# badge_ver_C.net
KiCad netlist of a schematic drawn in EAGLE
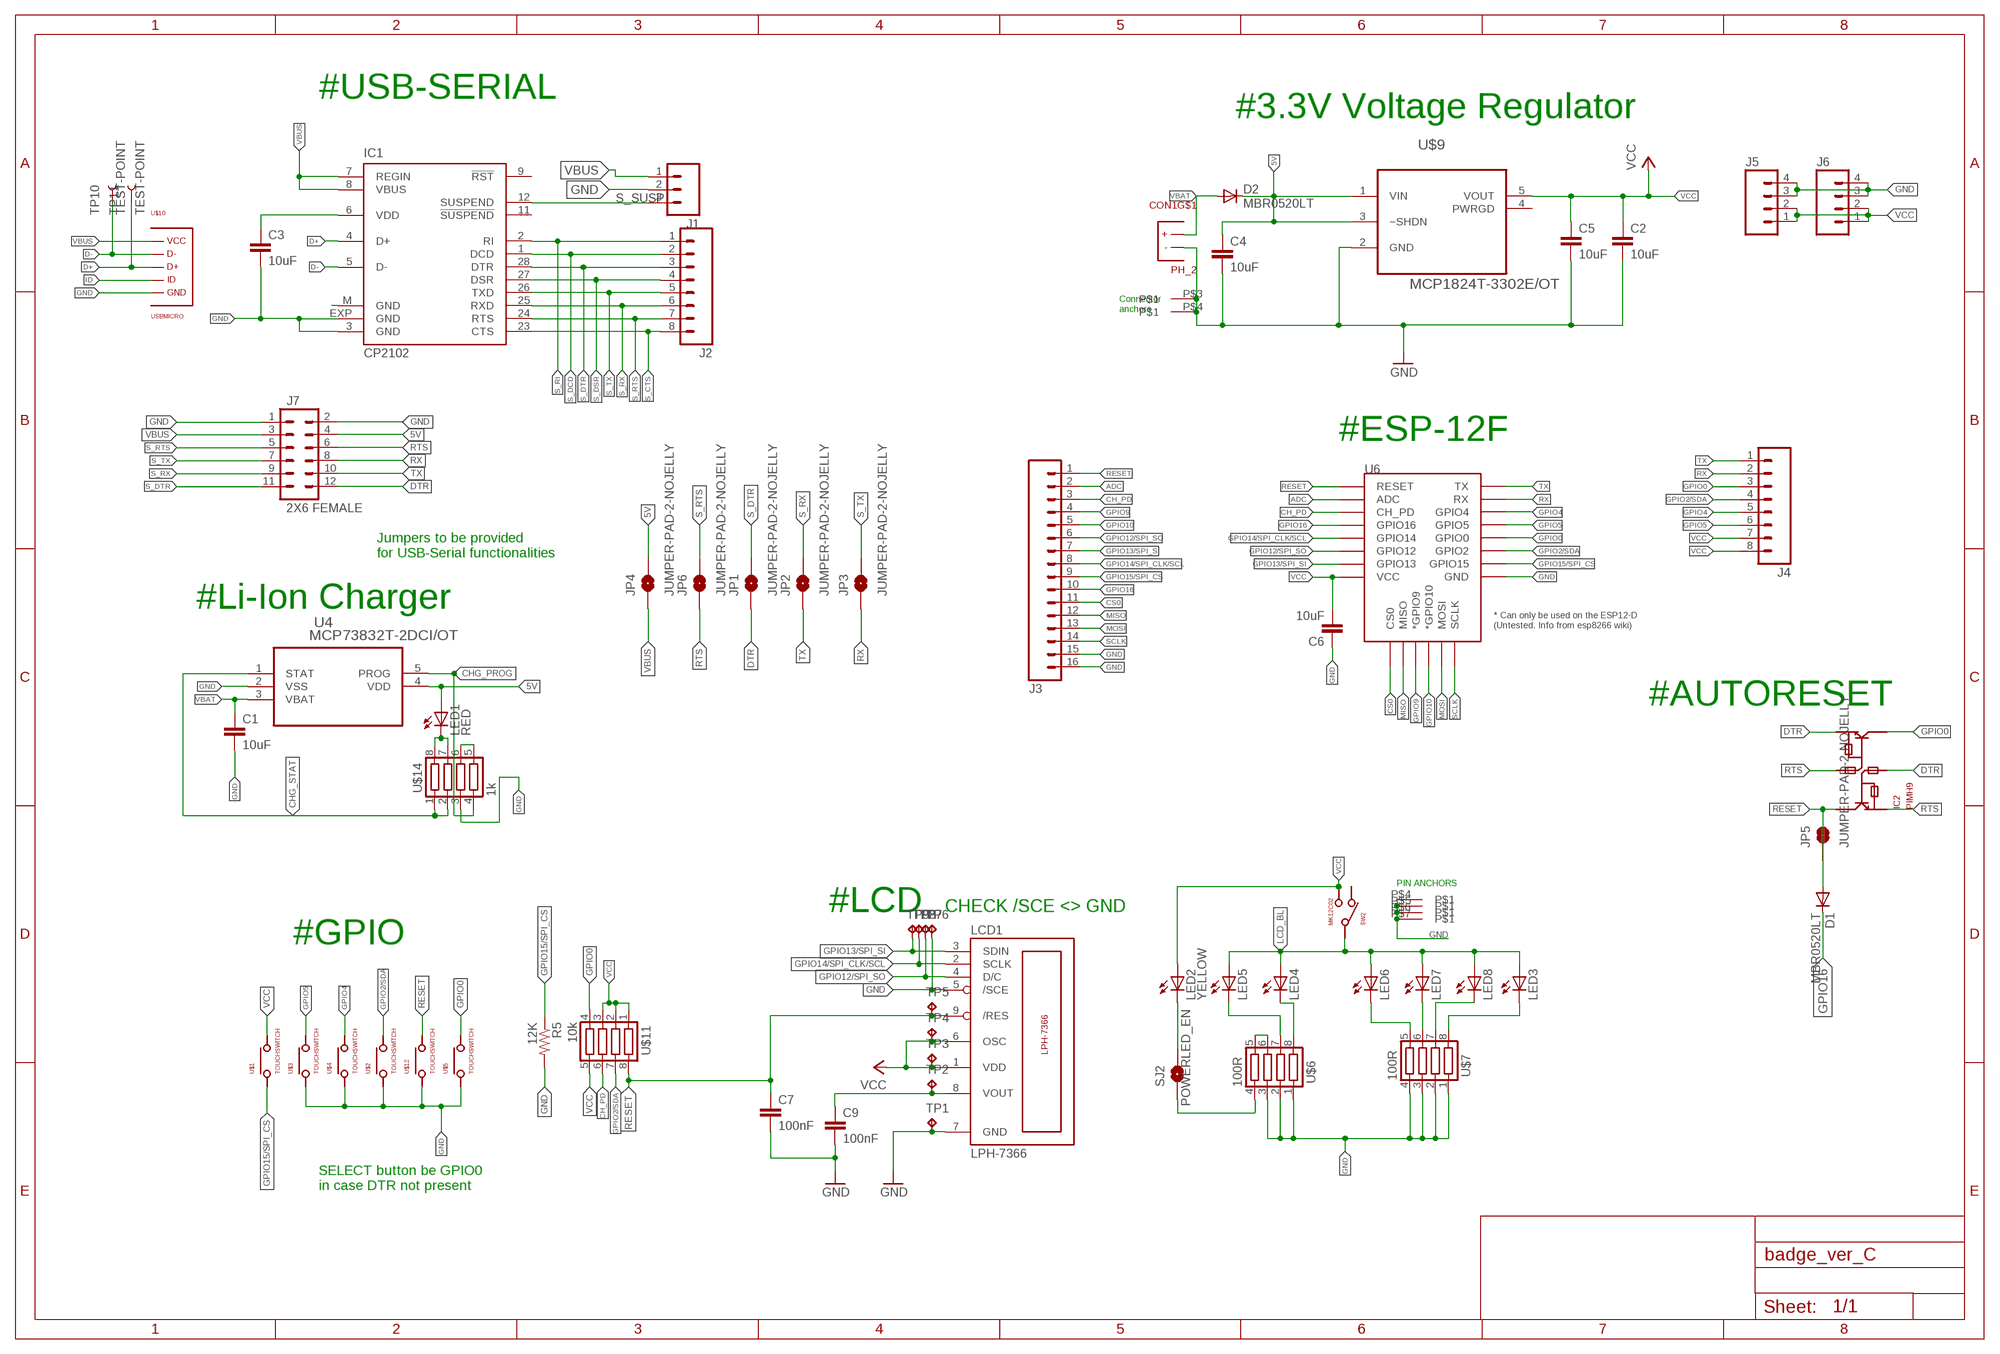
[diagram p0: schematic, sheet 1]

(export (version "E")
  (design (tool "Eeschema 10.0.6"))
  (components
    (comp (ref "C1")
      (value "10uF")
      (footprint "eagle-import:0805-CAP")
      (libsource (lib "eagle-import") (part "1UF-25V-10%(0805){dblquote}"))
    )
    (comp (ref "C2")
      (value "10uF")
      (footprint "eagle-import:0805-CAP")
      (libsource (lib "eagle-import") (part "1UF-25V-10%(0805){dblquote}"))
    )
    (comp (ref "C3")
      (value "10uF")
      (footprint "eagle-import:0805-CAP")
      (libsource (lib "eagle-import") (part "1UF-25V-10%(0805){dblquote}"))
    )
    (comp (ref "C4")
      (value "10uF")
      (footprint "eagle-import:0805-CAP")
      (libsource (lib "eagle-import") (part "1UF-25V-10%(0805){dblquote}"))
    )
    (comp (ref "C5")
      (value "10uF")
      (footprint "eagle-import:0805-CAP")
      (libsource (lib "eagle-import") (part "1UF-25V-10%(0805){dblquote}"))
    )
    (comp (ref "C6")
      (value "10uF")
      (footprint "eagle-import:0805-CAP")
      (libsource (lib "eagle-import") (part "1UF-25V-10%(0805){dblquote}"))
    )
    (comp (ref "C7")
      (value "100nF")
      (footprint "eagle-import:0805-CAP")
      (libsource (lib "eagle-import") (part "1UF-25V-10%(0805){dblquote}"))
    )
    (comp (ref "C9")
      (value "100nF")
      (footprint "eagle-import:0805-CAP")
      (libsource (lib "eagle-import") (part "1UF-25V-10%(0805){dblquote}"))
    )
    (comp (ref "CON1")
      (value "PH_2")
      (footprint "eagle-import:PH_2")
      (libsource (lib "eagle-import") (part "PH_2"))
    )
    (comp (ref "D1")
      (value "MBR0520LT")
      (footprint "eagle-import:SOD123")
      (libsource (lib "eagle-import") (part "MBR0520LT"))
    )
    (comp (ref "D2")
      (value "MBR0520LT")
      (footprint "eagle-import:SOD123")
      (libsource (lib "eagle-import") (part "MBR0520LT"))
    )
    (comp (ref "IC1")
      (value "CP2102")
      (footprint "eagle-import:MLP28")
      (fields (field (name "MF") "FARNELL") (field (name "MPN") "CP2102-GM"))
      (libsource (lib "eagle-import") (part "CP2102"))
    )
    (comp (ref "IC2")
      (value "PIMH9")
      (footprint "eagle-import:SOT457")
      (libsource (lib "eagle-import") (part "PIMH9"))
    )
    (comp (ref "J1")
      (value "M03PTH")
      (footprint "eagle-import:1X03")
      (libsource (lib "eagle-import") (part "M03PTH"))
    )
    (comp (ref "J2")
      (value "M08SILK_FEMALE_PTH")
      (footprint "eagle-import:1X08")
      (libsource (lib "eagle-import") (part "M08SILK_FEMALE_PTH"))
    )
    (comp (ref "J3")
      (value "M16PTH")
      (footprint "eagle-import:1X16")
      (libsource (lib "eagle-import") (part "M16PTH"))
    )
    (comp (ref "J4")
      (value "M08")
      (footprint "eagle-import:1X08_ROUND")
      (libsource (lib "eagle-import") (part "M08"))
    )
    (comp (ref "J5")
      (value "M04PTH")
      (footprint "eagle-import:1X04")
      (libsource (lib "eagle-import") (part "M04PTH"))
    )
    (comp (ref "J6")
      (value "M04PTH")
      (footprint "eagle-import:1X04")
      (libsource (lib "eagle-import") (part "M04PTH"))
    )
    (comp (ref "J7")
      (value "2X6 FEMALE")
      (footprint "eagle-import:2X6")
      (libsource (lib "eagle-import") (part "M06X2PTH_FEMALE"))
    )
    (comp (ref "JP1")
      (value "JUMPER-PAD-2-NOJELLY")
      (footprint "eagle-import:JELLYPAD-JUMPER-2-NO_NO_SILK")
      (libsource (lib "eagle-import") (part "JUMPER-PAD-2-NOJELLY"))
    )
    (comp (ref "JP2")
      (value "JUMPER-PAD-2-NOJELLY")
      (footprint "eagle-import:JELLYPAD-JUMPER-2-NO_NO_SILK")
      (libsource (lib "eagle-import") (part "JUMPER-PAD-2-NOJELLY"))
    )
    (comp (ref "JP3")
      (value "JUMPER-PAD-2-NOJELLY")
      (footprint "eagle-import:JELLYPAD-JUMPER-2-NO_NO_SILK")
      (libsource (lib "eagle-import") (part "JUMPER-PAD-2-NOJELLY"))
    )
    (comp (ref "JP4")
      (value "JUMPER-PAD-2-NOJELLY")
      (footprint "eagle-import:JELLYPAD-JUMPER-2-NO_NO_SILK")
      (libsource (lib "eagle-import") (part "JUMPER-PAD-2-NOJELLY"))
    )
    (comp (ref "JP5")
      (value "JUMPER-PAD-2-NOJELLY")
      (footprint "eagle-import:JELLYPAD-JUMPER-2-NO_NO_SILK")
      (libsource (lib "eagle-import") (part "JUMPER-PAD-2-NOJELLY"))
    )
    (comp (ref "JP6")
      (value "JUMPER-PAD-2-NOJELLY")
      (footprint "eagle-import:JELLYPAD-JUMPER-2-NO_NO_SILK")
      (libsource (lib "eagle-import") (part "JUMPER-PAD-2-NOJELLY"))
    )
    (comp (ref "LCD1")
      (value "LPH-7366")
      (footprint "eagle-import:LPH-7366")
      (libsource (lib "eagle-import") (part "LPH-7366"))
    )
    (comp (ref "LED1")
      (value "RED")
      (footprint "eagle-import:SML0805")
      (libsource (lib "eagle-import") (part "LEDSML0805"))
    )
    (comp (ref "LED2")
      (value "YELLOW")
      (footprint "eagle-import:SML0805")
      (libsource (lib "eagle-import") (part "LEDSML0805"))
    )
    (comp (ref "LED3")
      (value "LEDSML0805")
      (footprint "eagle-import:SML0805")
      (libsource (lib "eagle-import") (part "LEDSML0805"))
    )
    (comp (ref "LED4")
      (value "LEDSML0805")
      (footprint "eagle-import:SML0805")
      (libsource (lib "eagle-import") (part "LEDSML0805"))
    )
    (comp (ref "LED5")
      (value "LEDSML0805")
      (footprint "eagle-import:SML0805")
      (libsource (lib "eagle-import") (part "LEDSML0805"))
    )
    (comp (ref "LED6")
      (value "LEDSML0805")
      (footprint "eagle-import:SML0805")
      (libsource (lib "eagle-import") (part "LEDSML0805"))
    )
    (comp (ref "LED7")
      (value "LEDSML0805")
      (footprint "eagle-import:SML0805")
      (libsource (lib "eagle-import") (part "LEDSML0805"))
    )
    (comp (ref "LED8")
      (value "LEDSML0805")
      (footprint "eagle-import:SML0805")
      (libsource (lib "eagle-import") (part "LEDSML0805"))
    )
    (comp (ref "R5")
      (value "12K")
      (footprint "eagle-import:0805")
      (libsource (lib "eagle-import") (part "RESISTOR0805-RES"))
    )
    (comp (ref "SJ2")
      (value "POWERLED_EN")
      (footprint "eagle-import:SJ_2S-TRACE")
      (libsource (lib "eagle-import") (part "SOLDERJUMPERTRACE"))
    )
    (comp (ref "SW2")
      (value "MK12C02")
      (footprint "eagle-import:MK12C02")
      (libsource (lib "eagle-import") (part "MK12C02"))
    )
    (comp (ref "TP1")
      (value "TPB1,27")
      (footprint "eagle-import:B1,27")
      (libsource (lib "eagle-import") (part "TPB1,27"))
    )
    (comp (ref "TP2")
      (value "TPB1,27")
      (footprint "eagle-import:B1,27")
      (libsource (lib "eagle-import") (part "TPB1,27"))
    )
    (comp (ref "TP3")
      (value "TPB1,27")
      (footprint "eagle-import:B1,27")
      (libsource (lib "eagle-import") (part "TPB1,27"))
    )
    (comp (ref "TP4")
      (value "TPB1,27")
      (footprint "eagle-import:B1,27")
      (libsource (lib "eagle-import") (part "TPB1,27"))
    )
    (comp (ref "TP5")
      (value "TPB1,27")
      (footprint "eagle-import:B1,27")
      (libsource (lib "eagle-import") (part "TPB1,27"))
    )
    (comp (ref "TP6")
      (value "TPB1,27")
      (footprint "eagle-import:B1,27")
      (libsource (lib "eagle-import") (part "TPB1,27"))
    )
    (comp (ref "TP7")
      (value "TPB1,27")
      (footprint "eagle-import:B1,27")
      (libsource (lib "eagle-import") (part "TPB1,27"))
    )
    (comp (ref "TP8")
      (value "TPB1,27")
      (footprint "eagle-import:B1,27")
      (libsource (lib "eagle-import") (part "TPB1,27"))
    )
    (comp (ref "TP9")
      (value "TPB1,27")
      (footprint "eagle-import:B1,27")
      (libsource (lib "eagle-import") (part "TPB1,27"))
    )
    (comp (ref "TP10")
      (value "TEST-POINT")
      (footprint "eagle-import:PAD.02X.02_JELLY")
      (libsource (lib "eagle-import") (part "TEST-POINT"))
    )
    (comp (ref "TP11")
      (value "TEST-POINT")
      (footprint "eagle-import:PAD.02X.02_JELLY")
      (libsource (lib "eagle-import") (part "TEST-POINT"))
    )
    (comp (ref "U$1")
      (value "TOUCHSWITCH")
      (footprint "eagle-import:EVQQWN03W")
      (libsource (lib "eagle-import") (part "TOUCHSWITCH"))
    )
    (comp (ref "U$2")
      (value "TOUCHSWITCH")
      (footprint "eagle-import:EVQQWN03W")
      (libsource (lib "eagle-import") (part "TOUCHSWITCH"))
    )
    (comp (ref "U$3")
      (value "TOUCHSWITCH")
      (footprint "eagle-import:EVQQWN03W")
      (libsource (lib "eagle-import") (part "TOUCHSWITCH"))
    )
    (comp (ref "U$4")
      (value "TOUCHSWITCH")
      (footprint "eagle-import:EVQQWN03W")
      (libsource (lib "eagle-import") (part "TOUCHSWITCH"))
    )
    (comp (ref "U$5")
      (value "TOUCHSWITCH")
      (footprint "eagle-import:EVQQWN03W")
      (libsource (lib "eagle-import") (part "TOUCHSWITCH"))
    )
    (comp (ref "U$6")
      (value "100R")
      (footprint "eagle-import:YC164")
      (libsource (lib "eagle-import") (part "RES_ARR"))
    )
    (comp (ref "U$7")
      (value "100R")
      (footprint "eagle-import:YC164")
      (libsource (lib "eagle-import") (part "RES_ARR"))
    )
    (comp (ref "U$9")
      (value "MCP1824T-3302E/OT")
      (footprint "eagle-import:SOT95P270X145-5N")
      (libsource (lib "eagle-import") (part "MCP1824T-3302E/OT"))
    )
    (comp (ref "U$10")
      (value "USBMICRO")
      (footprint "eagle-import:USBMICRO")
      (libsource (lib "eagle-import") (part "USBMICRO"))
    )
    (comp (ref "U$11")
      (value "10k")
      (footprint "eagle-import:YC164")
      (libsource (lib "eagle-import") (part "RES_ARR"))
    )
    (comp (ref "U$12")
      (value "TOUCHSWITCH")
      (footprint "eagle-import:EVQQWN03W")
      (libsource (lib "eagle-import") (part "TOUCHSWITCH"))
    )
    (comp (ref "U$14")
      (value "1k")
      (footprint "eagle-import:YC164")
      (libsource (lib "eagle-import") (part "RES_ARR"))
    )
    (comp (ref "U4")
      (value "MCP73832T-2DCI/OT")
      (footprint "eagle-import:SOT95P300X145-5N")
      (libsource (lib "eagle-import") (part "MCP73832T-2DCI/OT"))
    )
    (comp (ref "U6")
      (value "ESP12ESMD")
      (footprint "eagle-import:ESP12E-SMD")
      (libsource (lib "eagle-import") (part "ESP12ESMD"))
    )
  )
  (nets
    (net (code "1") (name "/S_SUSP") (class "Default")
      (node (ref "IC1") (pin "12") (pinfunction "SUSPEND_12") (pintype "output"))
      (node (ref "J1") (pin "3") (pinfunction "3_3") (pintype "passive"))
    )
    (net (code "2") (name "5V") (class "Default")
      (node (ref "C4") (pin "1") (pinfunction "1_1") (pintype "passive"))
      (node (ref "D2") (pin "C") (pinfunction "C_C") (pintype "passive"))
      (node (ref "J7") (pin "4") (pinfunction "4_4") (pintype "passive"))
      (node (ref "JP4") (pin "2") (pinfunction "2_2") (pintype "passive"))
      (node (ref "LED1") (pin "A") (pinfunction "A_A") (pintype "passive"))
      (node (ref "U$9") (pin "1") (pinfunction "VIN_1") (pintype "input"))
      (node (ref "U$9") (pin "3") (pinfunction "~{SHDN}_3") (pintype "input"))
      (node (ref "U4") (pin "4") (pinfunction "VDD_4") (pintype "power_in"))
    )
    (net (code "3") (name "ADC") (class "Default")
      (node (ref "J3") (pin "2") (pinfunction "2_2") (pintype "passive"))
      (node (ref "U6") (pin "ADC") (pinfunction "ADC_ADC") (pintype "bidirectional"))
    )
    (net (code "4") (name "CHG_PROG") (class "Default")
      (node (ref "U$14") (pin "4") (pinfunction "4_4") (pintype "passive"))
      (node (ref "U4") (pin "5") (pinfunction "PROG_5") (pintype "input"))
    )
    (net (code "5") (name "CHG_STAT") (class "Default")
      (node (ref "U$14") (pin "1") (pinfunction "1_1") (pintype "passive"))
      (node (ref "U$14") (pin "2") (pinfunction "2_2") (pintype "passive"))
      (node (ref "U4") (pin "1") (pinfunction "STAT_1") (pintype "input"))
    )
    (net (code "6") (name "CH_PD") (class "Default")
      (node (ref "J3") (pin "3") (pinfunction "3_3") (pintype "passive"))
      (node (ref "U$11") (pin "6") (pinfunction "6_6") (pintype "passive"))
      (node (ref "U6") (pin "CH_PD") (pinfunction "CH_PD_CH_PD") (pintype "bidirectional"))
    )
    (net (code "7") (name "CS0") (class "Default")
      (node (ref "J3") (pin "11") (pinfunction "11_11") (pintype "passive"))
      (node (ref "U6") (pin "CS0") (pinfunction "CS0_CS0") (pintype "bidirectional"))
    )
    (net (code "8") (name "D+") (class "Default")
      (node (ref "IC1") (pin "4") (pinfunction "D+_4") (pintype "bidirectional"))
      (node (ref "TP11") (pin "P$1") (pinfunction "1_P$1") (pintype "bidirectional"))
      (node (ref "U$10") (pin "P$D+") (pinfunction "P$D+_P$D+") (pintype "bidirectional"))
    )
    (net (code "9") (name "D-") (class "Default")
      (node (ref "IC1") (pin "5") (pinfunction "D-_5") (pintype "bidirectional"))
      (node (ref "TP10") (pin "P$1") (pinfunction "1_P$1") (pintype "bidirectional"))
      (node (ref "U$10") (pin "P$D-") (pinfunction "P$D-_P$D-") (pintype "bidirectional"))
    )
    (net (code "10") (name "DTR") (class "Default")
      (node (ref "IC2") (pin "P$2") (pinfunction "P$2_P$2") (pintype "bidirectional"))
      (node (ref "IC2") (pin "P$4") (pinfunction "P$4_P$4") (pintype "bidirectional"))
      (node (ref "J7") (pin "12") (pinfunction "12_12") (pintype "passive"))
      (node (ref "JP1") (pin "1") (pinfunction "1_1") (pintype "passive"))
    )
    (net (code "11") (name "GND") (class "Default")
      (node (ref "C1") (pin "2") (pinfunction "2_2") (pintype "passive"))
      (node (ref "C2") (pin "2") (pinfunction "2_2") (pintype "passive"))
      (node (ref "C3") (pin "2") (pinfunction "2_2") (pintype "passive"))
      (node (ref "C4") (pin "2") (pinfunction "2_2") (pintype "passive"))
      (node (ref "C5") (pin "2") (pinfunction "2_2") (pintype "passive"))
      (node (ref "C6") (pin "1") (pinfunction "1_1") (pintype "passive"))
      (node (ref "C7") (pin "2") (pinfunction "2_2") (pintype "passive"))
      (node (ref "C9") (pin "2") (pinfunction "2_2") (pintype "passive"))
      (node (ref "CON1") (pin "P$1") (pinfunction "P$2_P$1") (pintype "bidirectional"))
      (node (ref "CON1") (pin "P$3") (pinfunction "P$1_P$3") (pintype "bidirectional"))
      (node (ref "CON1") (pin "P$4") (pinfunction "P$1_P$4") (pintype "bidirectional"))
      (node (ref "IC1") (pin "3") (pinfunction "GND_3") (pintype "power_in"))
      (node (ref "IC1") (pin "EXP") (pinfunction "GND_EXP") (pintype "power_in"))
      (node (ref "J1") (pin "2") (pinfunction "2_2") (pintype "passive"))
      (node (ref "J3") (pin "15") (pinfunction "15_15") (pintype "passive"))
      (node (ref "J3") (pin "16") (pinfunction "16_16") (pintype "passive"))
      (node (ref "J5") (pin "3") (pinfunction "3_3") (pintype "passive"))
      (node (ref "J5") (pin "4") (pinfunction "4_4") (pintype "passive"))
      (node (ref "J6") (pin "3") (pinfunction "3_3") (pintype "passive"))
      (node (ref "J6") (pin "4") (pinfunction "4_4") (pintype "passive"))
      (node (ref "J7") (pin "1") (pinfunction "1_1") (pintype "passive"))
      (node (ref "J7") (pin "2") (pinfunction "2_2") (pintype "passive"))
      (node (ref "LCD1") (pin "5") (pinfunction "/SCE_5") (pintype "input"))
      (node (ref "LCD1") (pin "7") (pinfunction "GND_7") (pintype "power_in"))
      (node (ref "R5") (pin "2") (pinfunction "2_2") (pintype "passive"))
      (node (ref "SW2") (pin "P$4") (pinfunction "P$1_P$4") (pintype "bidirectional"))
      (node (ref "SW2") (pin "P$5") (pinfunction "P$1_P$5") (pintype "bidirectional"))
      (node (ref "SW2") (pin "P$6") (pinfunction "P$1_P$6") (pintype "bidirectional"))
      (node (ref "SW2") (pin "P$7") (pinfunction "P$1_P$7") (pintype "bidirectional"))
      (node (ref "TP1") (pin "TP") (pinfunction "TP_TP") (pintype "input"))
      (node (ref "TP6") (pin "TP") (pinfunction "TP_TP") (pintype "input"))
      (node (ref "U$10") (pin "P$GND") (pinfunction "P$GND_P$GND") (pintype "bidirectional"))
      (node (ref "U$12") (pin "P$1") (pinfunction "P$1_P$1") (pintype "bidirectional"))
      (node (ref "U$12") (pin "P$4") (pinfunction "P$1_P$4") (pintype "bidirectional"))
      (node (ref "U$14") (pin "3") (pinfunction "3_3") (pintype "passive"))
      (node (ref "U$2") (pin "P$1") (pinfunction "P$1_P$1") (pintype "bidirectional"))
      (node (ref "U$2") (pin "P$4") (pinfunction "P$1_P$4") (pintype "bidirectional"))
      (node (ref "U$3") (pin "P$1") (pinfunction "P$1_P$1") (pintype "bidirectional"))
      (node (ref "U$3") (pin "P$4") (pinfunction "P$1_P$4") (pintype "bidirectional"))
      (node (ref "U$4") (pin "P$1") (pinfunction "P$1_P$1") (pintype "bidirectional"))
      (node (ref "U$4") (pin "P$4") (pinfunction "P$1_P$4") (pintype "bidirectional"))
      (node (ref "U$5") (pin "P$1") (pinfunction "P$1_P$1") (pintype "bidirectional"))
      (node (ref "U$5") (pin "P$4") (pinfunction "P$1_P$4") (pintype "bidirectional"))
      (node (ref "U$6") (pin "1") (pinfunction "1_1") (pintype "passive"))
      (node (ref "U$6") (pin "2") (pinfunction "2_2") (pintype "passive"))
      (node (ref "U$6") (pin "3") (pinfunction "3_3") (pintype "passive"))
      (node (ref "U$7") (pin "1") (pinfunction "1_1") (pintype "passive"))
      (node (ref "U$7") (pin "2") (pinfunction "2_2") (pintype "passive"))
      (node (ref "U$7") (pin "3") (pinfunction "3_3") (pintype "passive"))
      (node (ref "U$7") (pin "4") (pinfunction "4_4") (pintype "passive"))
      (node (ref "U$9") (pin "2") (pinfunction "GND_2") (pintype "passive"))
      (node (ref "U4") (pin "2") (pinfunction "VSS_2") (pintype "passive"))
      (node (ref "U6") (pin "GND") (pinfunction "GND_GND") (pintype "bidirectional"))
    )
    (net (code "12") (name "GPIO0") (class "Default")
      (node (ref "IC2") (pin "P$3") (pinfunction "P$3_P$3") (pintype "bidirectional"))
      (node (ref "J4") (pin "3") (pinfunction "3_3") (pintype "passive"))
      (node (ref "U$11") (pin "4") (pinfunction "4_4") (pintype "passive"))
      (node (ref "U$5") (pin "P$2") (pinfunction "P$2_P$2") (pintype "bidirectional"))
      (node (ref "U$5") (pin "P$3") (pinfunction "P$2_P$3") (pintype "bidirectional"))
      (node (ref "U6") (pin "GPIO0") (pinfunction "GPIO0_GPIO0") (pintype "bidirectional"))
    )
    (net (code "13") (name "GPIO2{slash}SDA") (class "Default")
      (node (ref "J4") (pin "4") (pinfunction "4_4") (pintype "passive"))
      (node (ref "U$11") (pin "7") (pinfunction "7_7") (pintype "passive"))
      (node (ref "U$2") (pin "P$2") (pinfunction "P$2_P$2") (pintype "bidirectional"))
      (node (ref "U$2") (pin "P$3") (pinfunction "P$2_P$3") (pintype "bidirectional"))
      (node (ref "U6") (pin "GPIO2") (pinfunction "GPIO2_GPIO2") (pintype "bidirectional"))
    )
    (net (code "14") (name "GPIO4") (class "Default")
      (node (ref "J4") (pin "5") (pinfunction "5_5") (pintype "passive"))
      (node (ref "U$4") (pin "P$2") (pinfunction "P$2_P$2") (pintype "bidirectional"))
      (node (ref "U$4") (pin "P$3") (pinfunction "P$2_P$3") (pintype "bidirectional"))
      (node (ref "U6") (pin "GPIO4") (pinfunction "GPIO4_GPIO4") (pintype "bidirectional"))
    )
    (net (code "15") (name "GPIO5") (class "Default")
      (node (ref "J4") (pin "6") (pinfunction "6_6") (pintype "passive"))
      (node (ref "U$3") (pin "P$2") (pinfunction "P$2_P$2") (pintype "bidirectional"))
      (node (ref "U$3") (pin "P$3") (pinfunction "P$2_P$3") (pintype "bidirectional"))
      (node (ref "U6") (pin "GPIO5") (pinfunction "GPIO5_GPIO5") (pintype "bidirectional"))
    )
    (net (code "16") (name "GPIO9") (class "Default")
      (node (ref "J3") (pin "4") (pinfunction "4_4") (pintype "passive"))
      (node (ref "U6") (pin "GPIO9") (pinfunction "*GPIO9_GPIO9") (pintype "bidirectional"))
    )
    (net (code "17") (name "GPIO10") (class "Default")
      (node (ref "J3") (pin "5") (pinfunction "5_5") (pintype "passive"))
      (node (ref "U6") (pin "GPIO10") (pinfunction "*GPIO10_GPIO10") (pintype "bidirectional"))
    )
    (net (code "18") (name "GPIO12{slash}SPI_SO") (class "Default")
      (node (ref "J3") (pin "6") (pinfunction "6_6") (pintype "passive"))
      (node (ref "LCD1") (pin "4") (pinfunction "D/C_4") (pintype "input"))
      (node (ref "TP7") (pin "TP") (pinfunction "TP_TP") (pintype "input"))
      (node (ref "U6") (pin "GPIO12") (pinfunction "GPIO12_GPIO12") (pintype "bidirectional"))
    )
    (net (code "19") (name "GPIO13{slash}SPI_SI") (class "Default")
      (node (ref "J3") (pin "7") (pinfunction "7_7") (pintype "passive"))
      (node (ref "LCD1") (pin "3") (pinfunction "SDIN_3") (pintype "input"))
      (node (ref "TP9") (pin "TP") (pinfunction "TP_TP") (pintype "input"))
      (node (ref "U6") (pin "GPIO13") (pinfunction "GPIO13_GPIO13") (pintype "bidirectional"))
    )
    (net (code "20") (name "GPIO14{slash}SPI_CLK{slash}SCL") (class "Default")
      (node (ref "J3") (pin "8") (pinfunction "8_8") (pintype "passive"))
      (node (ref "LCD1") (pin "2") (pinfunction "SCLK_2") (pintype "input"))
      (node (ref "TP8") (pin "TP") (pinfunction "TP_TP") (pintype "input"))
      (node (ref "U6") (pin "GPIO14") (pinfunction "GPIO14_GPIO14") (pintype "bidirectional"))
    )
    (net (code "21") (name "GPIO15{slash}SPI_CS") (class "Default")
      (node (ref "J3") (pin "9") (pinfunction "9_9") (pintype "passive"))
      (node (ref "R5") (pin "1") (pinfunction "1_1") (pintype "passive"))
      (node (ref "U$1") (pin "P$1") (pinfunction "P$1_P$1") (pintype "bidirectional"))
      (node (ref "U$1") (pin "P$4") (pinfunction "P$1_P$4") (pintype "bidirectional"))
      (node (ref "U6") (pin "GPIO15") (pinfunction "GPIO15_GPIO15") (pintype "bidirectional"))
    )
    (net (code "22") (name "GPIO16") (class "Default")
      (node (ref "D1") (pin "C") (pinfunction "C_C") (pintype "passive"))
      (node (ref "J3") (pin "10") (pinfunction "10_10") (pintype "passive"))
      (node (ref "U6") (pin "GPIO16") (pinfunction "GPIO16_GPIO16") (pintype "bidirectional"))
    )
    (net (code "23") (name "ID") (class "Default")
      (node (ref "U$10") (pin "P$ID") (pinfunction "P$ID_P$ID") (pintype "bidirectional"))
    )
    (net (code "24") (name "LCD_BL") (class "Default")
      (node (ref "LED3") (pin "A") (pinfunction "A_A") (pintype "passive"))
      (node (ref "LED4") (pin "A") (pinfunction "A_A") (pintype "passive"))
      (node (ref "LED5") (pin "A") (pinfunction "A_A") (pintype "passive"))
      (node (ref "LED6") (pin "A") (pinfunction "A_A") (pintype "passive"))
      (node (ref "LED7") (pin "A") (pinfunction "A_A") (pintype "passive"))
      (node (ref "LED8") (pin "A") (pinfunction "A_A") (pintype "passive"))
      (node (ref "SW2") (pin "P$2") (pinfunction "P$1_P$2") (pintype "bidirectional"))
    )
    (net (code "25") (name "MISO") (class "Default")
      (node (ref "J3") (pin "12") (pinfunction "12_12") (pintype "passive"))
      (node (ref "U6") (pin "MISO") (pinfunction "MISO_MISO") (pintype "bidirectional"))
    )
    (net (code "26") (name "MOSI") (class "Default")
      (node (ref "J3") (pin "13") (pinfunction "13_13") (pintype "passive"))
      (node (ref "U6") (pin "MOSI") (pinfunction "MOSI_MOSI") (pintype "bidirectional"))
    )
    (net (code "27") (name "Net-(IC1-VDD)") (class "Default")
      (node (ref "C3") (pin "1") (pinfunction "1_1") (pintype "passive"))
      (node (ref "IC1") (pin "6") (pinfunction "VDD_6") (pintype "power_in"))
    )
    (net (code "28") (name "Net-(LCD1-VOUT)") (class "Default")
      (node (ref "C9") (pin "1") (pinfunction "1_1") (pintype "passive"))
      (node (ref "LCD1") (pin "8") (pinfunction "VOUT_8") (pintype "passive"))
      (node (ref "TP2") (pin "TP") (pinfunction "TP_TP") (pintype "input"))
    )
    (net (code "29") (name "Net-(LED1-PadC)") (class "Default")
      (node (ref "LED1") (pin "C") (pinfunction "C_C") (pintype "passive"))
      (node (ref "U$14") (pin "7") (pinfunction "7_7") (pintype "passive"))
      (node (ref "U$14") (pin "8") (pinfunction "8_8") (pintype "passive"))
    )
    (net (code "30") (name "Net-(LED2-PadC)") (class "Default")
      (node (ref "LED2") (pin "C") (pinfunction "C_C") (pintype "passive"))
      (node (ref "SJ2") (pin "2") (pinfunction "2_2") (pintype "passive"))
    )
    (net (code "31") (name "Net-(LED3-PadC)") (class "Default")
      (node (ref "LED3") (pin "C") (pinfunction "C_C") (pintype "passive"))
      (node (ref "U$7") (pin "8") (pinfunction "8_8") (pintype "passive"))
    )
    (net (code "32") (name "Net-(LED4-PadC)") (class "Default")
      (node (ref "LED4") (pin "C") (pinfunction "C_C") (pintype "passive"))
      (node (ref "U$6") (pin "8") (pinfunction "8_8") (pintype "passive"))
    )
    (net (code "33") (name "Net-(LED5-PadC)") (class "Default")
      (node (ref "LED5") (pin "C") (pinfunction "C_C") (pintype "passive"))
      (node (ref "U$6") (pin "7") (pinfunction "7_7") (pintype "passive"))
    )
    (net (code "34") (name "Net-(LED6-PadC)") (class "Default")
      (node (ref "LED6") (pin "C") (pinfunction "C_C") (pintype "passive"))
      (node (ref "U$7") (pin "5") (pinfunction "5_5") (pintype "passive"))
    )
    (net (code "35") (name "Net-(LED7-PadC)") (class "Default")
      (node (ref "LED7") (pin "C") (pinfunction "C_C") (pintype "passive"))
      (node (ref "U$7") (pin "6") (pinfunction "6_6") (pintype "passive"))
    )
    (net (code "36") (name "Net-(LED8-PadC)") (class "Default")
      (node (ref "LED8") (pin "C") (pinfunction "C_C") (pintype "passive"))
      (node (ref "U$7") (pin "7") (pinfunction "7_7") (pintype "passive"))
    )
    (net (code "37") (name "Net-(SJ2-Pad1)") (class "Default")
      (node (ref "SJ2") (pin "1") (pinfunction "1_1") (pintype "passive"))
      (node (ref "U$6") (pin "4") (pinfunction "4_4") (pintype "passive"))
    )
    (net (code "38") (name "Net-(U$6-Pad5)") (class "Default")
      (node (ref "U$6") (pin "5") (pinfunction "5_5") (pintype "passive"))
      (node (ref "U$6") (pin "6") (pinfunction "6_6") (pintype "passive"))
    )
    (net (code "39") (name "Net-(U$14-Pad5)") (class "Default")
      (node (ref "U$14") (pin "5") (pinfunction "5_5") (pintype "passive"))
      (node (ref "U$14") (pin "6") (pinfunction "6_6") (pintype "passive"))
    )
    (net (code "40") (name "RESET") (class "Default")
      (node (ref "C7") (pin "1") (pinfunction "1_1") (pintype "passive"))
      (node (ref "D1") (pin "A") (pinfunction "A_A") (pintype "passive"))
      (node (ref "IC2") (pin "P$6") (pinfunction "P$6_P$6") (pintype "bidirectional"))
      (node (ref "J3") (pin "1") (pinfunction "1_1") (pintype "passive"))
      (node (ref "JP5") (pin "1") (pinfunction "1_1") (pintype "passive"))
      (node (ref "JP5") (pin "2") (pinfunction "2_2") (pintype "passive"))
      (node (ref "LCD1") (pin "9") (pinfunction "/RES_9") (pintype "input"))
      (node (ref "TP5") (pin "TP") (pinfunction "TP_TP") (pintype "input"))
      (node (ref "U$11") (pin "8") (pinfunction "8_8") (pintype "passive"))
      (node (ref "U$12") (pin "P$2") (pinfunction "P$2_P$2") (pintype "bidirectional"))
      (node (ref "U$12") (pin "P$3") (pinfunction "P$2_P$3") (pintype "bidirectional"))
      (node (ref "U6") (pin "RESET") (pinfunction "RESET_RESET") (pintype "bidirectional"))
    )
    (net (code "41") (name "RTS") (class "Default")
      (node (ref "IC2") (pin "P$1") (pinfunction "P$1_P$1") (pintype "bidirectional"))
      (node (ref "IC2") (pin "P$5") (pinfunction "P$5_P$5") (pintype "bidirectional"))
      (node (ref "J7") (pin "6") (pinfunction "6_6") (pintype "passive"))
      (node (ref "JP6") (pin "1") (pinfunction "1_1") (pintype "passive"))
    )
    (net (code "42") (name "RX") (class "Default")
      (node (ref "J4") (pin "2") (pinfunction "2_2") (pintype "passive"))
      (node (ref "J7") (pin "8") (pinfunction "8_8") (pintype "passive"))
      (node (ref "JP3") (pin "1") (pinfunction "1_1") (pintype "passive"))
      (node (ref "U6") (pin "RXD0") (pinfunction "RX_RXD0") (pintype "bidirectional"))
    )
    (net (code "43") (name "SCLK") (class "Default")
      (node (ref "J3") (pin "14") (pinfunction "14_14") (pintype "passive"))
      (node (ref "U6") (pin "SCLK") (pinfunction "SCLK_SCLK") (pintype "bidirectional"))
    )
    (net (code "44") (name "S_CTS") (class "Default")
      (node (ref "IC1") (pin "23") (pinfunction "CTS_23") (pintype "input"))
      (node (ref "J2") (pin "8") (pinfunction "8_8") (pintype "passive"))
    )
    (net (code "45") (name "S_DCD") (class "Default")
      (node (ref "IC1") (pin "1") (pinfunction "DCD_1") (pintype "input"))
      (node (ref "J2") (pin "2") (pinfunction "2_2") (pintype "passive"))
    )
    (net (code "46") (name "S_DSR") (class "Default")
      (node (ref "IC1") (pin "27") (pinfunction "DSR_27") (pintype "input"))
      (node (ref "J2") (pin "4") (pinfunction "4_4") (pintype "passive"))
    )
    (net (code "47") (name "S_DTR") (class "Default")
      (node (ref "IC1") (pin "28") (pinfunction "DTR_28") (pintype "output"))
      (node (ref "J2") (pin "3") (pinfunction "3_3") (pintype "passive"))
      (node (ref "J7") (pin "11") (pinfunction "11_11") (pintype "passive"))
      (node (ref "JP1") (pin "2") (pinfunction "2_2") (pintype "passive"))
    )
    (net (code "48") (name "S_RI") (class "Default")
      (node (ref "IC1") (pin "2") (pinfunction "RI_2") (pintype "input"))
      (node (ref "J2") (pin "1") (pinfunction "1_1") (pintype "passive"))
    )
    (net (code "49") (name "S_RTS") (class "Default")
      (node (ref "IC1") (pin "24") (pinfunction "RTS_24") (pintype "output"))
      (node (ref "J2") (pin "7") (pinfunction "7_7") (pintype "passive"))
      (node (ref "J7") (pin "5") (pinfunction "5_5") (pintype "passive"))
      (node (ref "JP6") (pin "2") (pinfunction "2_2") (pintype "passive"))
    )
    (net (code "50") (name "S_RX") (class "Default")
      (node (ref "IC1") (pin "25") (pinfunction "RXD_25") (pintype "input"))
      (node (ref "J2") (pin "6") (pinfunction "6_6") (pintype "passive"))
      (node (ref "J7") (pin "9") (pinfunction "9_9") (pintype "passive"))
      (node (ref "JP2") (pin "2") (pinfunction "2_2") (pintype "passive"))
    )
    (net (code "51") (name "S_TX") (class "Default")
      (node (ref "IC1") (pin "26") (pinfunction "TXD_26") (pintype "output"))
      (node (ref "J2") (pin "5") (pinfunction "5_5") (pintype "passive"))
      (node (ref "J7") (pin "7") (pinfunction "7_7") (pintype "passive"))
      (node (ref "JP3") (pin "2") (pinfunction "2_2") (pintype "passive"))
    )
    (net (code "52") (name "TX") (class "Default")
      (node (ref "J4") (pin "1") (pinfunction "1_1") (pintype "passive"))
      (node (ref "J7") (pin "10") (pinfunction "10_10") (pintype "passive"))
      (node (ref "JP2") (pin "1") (pinfunction "1_1") (pintype "passive"))
      (node (ref "U6") (pin "TXD0") (pinfunction "TX_TXD0") (pintype "bidirectional"))
    )
    (net (code "53") (name "VBAT") (class "Default")
      (node (ref "C1") (pin "1") (pinfunction "1_1") (pintype "passive"))
      (node (ref "CON1") (pin "P$2") (pinfunction "P$1_P$2") (pintype "bidirectional"))
      (node (ref "D2") (pin "A") (pinfunction "A_A") (pintype "passive"))
      (node (ref "U4") (pin "3") (pinfunction "VBAT_3") (pintype "input"))
    )
    (net (code "54") (name "VBUS") (class "Default")
      (node (ref "IC1") (pin "7") (pinfunction "REGIN_7") (pintype "passive"))
      (node (ref "IC1") (pin "8") (pinfunction "VBUS_8") (pintype "input"))
      (node (ref "J1") (pin "1") (pinfunction "1_1") (pintype "passive"))
      (node (ref "J7") (pin "3") (pinfunction "3_3") (pintype "passive"))
      (node (ref "JP4") (pin "1") (pinfunction "1_1") (pintype "passive"))
      (node (ref "U$10") (pin "P$VCC") (pinfunction "P$VCC_P$VCC") (pintype "bidirectional"))
    )
    (net (code "55") (name "VCC") (class "Default")
      (node (ref "C2") (pin "1") (pinfunction "1_1") (pintype "passive"))
      (node (ref "C5") (pin "1") (pinfunction "1_1") (pintype "passive"))
      (node (ref "C6") (pin "2") (pinfunction "2_2") (pintype "passive"))
      (node (ref "J4") (pin "7") (pinfunction "7_7") (pintype "passive"))
      (node (ref "J4") (pin "8") (pinfunction "8_8") (pintype "passive"))
      (node (ref "J5") (pin "1") (pinfunction "1_1") (pintype "passive"))
      (node (ref "J5") (pin "2") (pinfunction "2_2") (pintype "passive"))
      (node (ref "J6") (pin "1") (pinfunction "1_1") (pintype "passive"))
      (node (ref "J6") (pin "2") (pinfunction "2_2") (pintype "passive"))
      (node (ref "LCD1") (pin "1") (pinfunction "VDD_1") (pintype "power_in"))
      (node (ref "LCD1") (pin "6") (pinfunction "OSC_6") (pintype "passive"))
      (node (ref "LED2") (pin "A") (pinfunction "A_A") (pintype "passive"))
      (node (ref "SW2") (pin "P$3") (pinfunction "P$3_P$3") (pintype "bidirectional"))
      (node (ref "TP3") (pin "TP") (pinfunction "TP_TP") (pintype "input"))
      (node (ref "TP4") (pin "TP") (pinfunction "TP_TP") (pintype "input"))
      (node (ref "U$1") (pin "P$2") (pinfunction "P$2_P$2") (pintype "bidirectional"))
      (node (ref "U$1") (pin "P$3") (pinfunction "P$2_P$3") (pintype "bidirectional"))
      (node (ref "U$11") (pin "1") (pinfunction "1_1") (pintype "passive"))
      (node (ref "U$11") (pin "2") (pinfunction "2_2") (pintype "passive"))
      (node (ref "U$11") (pin "3") (pinfunction "3_3") (pintype "passive"))
      (node (ref "U$11") (pin "5") (pinfunction "5_5") (pintype "passive"))
      (node (ref "U$9") (pin "5") (pinfunction "VOUT_5") (pintype "output"))
      (node (ref "U6") (pin "VCC") (pinfunction "VCC_VCC") (pintype "bidirectional"))
    )
    (net (code "56") (name "unconnected-(IC1-GND-PadM)") (class "Default")
      (node (ref "IC1") (pin "M") (pinfunction "GND_M") (pintype "power_in"))
    )
    (net (code "57") (name "unconnected-(IC1-~{RST}-Pad9)") (class "Default")
      (node (ref "IC1") (pin "9") (pinfunction "~{RST}_9") (pintype "bidirectional"))
    )
    (net (code "58") (name "unconnected-(IC1-~{SUSPEND}-Pad11)") (class "Default")
      (node (ref "IC1") (pin "11") (pinfunction "~{SUSPEND}_11") (pintype "output"))
    )
    (net (code "59") (name "unconnected-(SW2A-P$2-PadP$1)") (class "Default")
      (node (ref "SW2") (pin "P$1") (pinfunction "P$2_P$1") (pintype "bidirectional"))
    )
    (net (code "60") (name "unconnected-(U$9-PWRGD-Pad4)") (class "Default")
      (node (ref "U$9") (pin "4") (pinfunction "PWRGD_4") (pintype "output"))
    )
  )
)
